# S905D_MIC_V1_1.net
KiCad netlist of a schematic drawn in Altium Designer
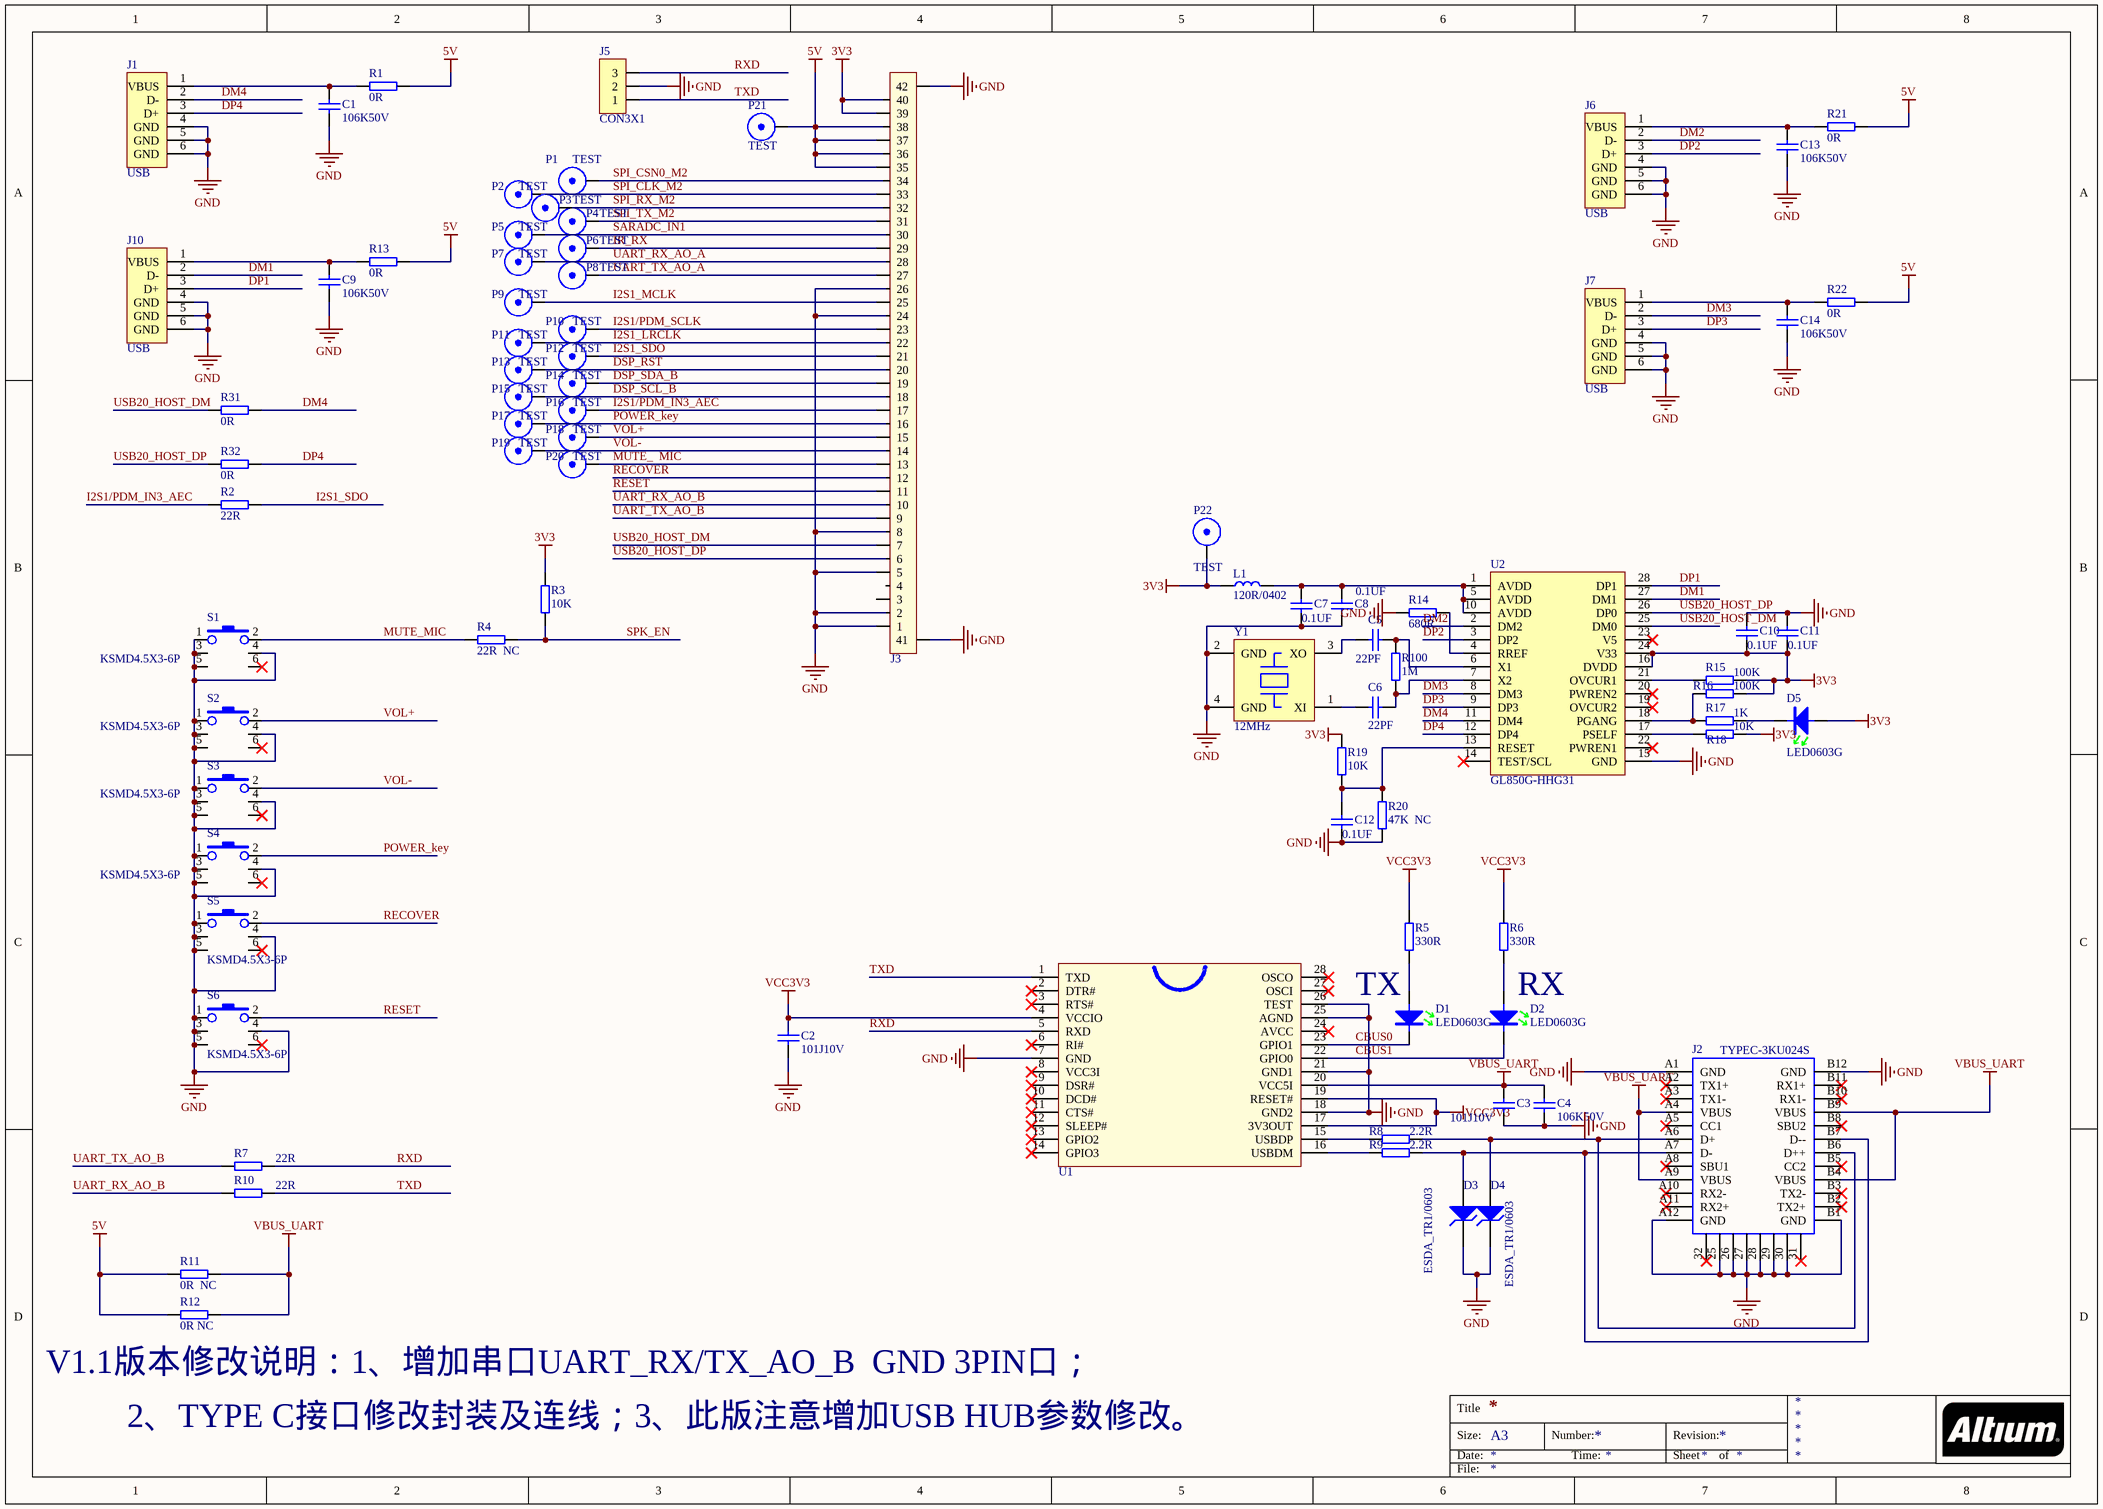
[diagram p0: S905D_MIC_V1.1.SchDoc]

(export (version "E")
  (design (tool "Eeschema 10.0.6"))
  (components
    (comp (ref "C1")
      (value "106K50V")
      (footprint "C0603")
      (description "贴片电容-陶瓷")
      (libsource (lib "AIWAC-bolsterV01") (part "C0603X7R-106K50V"))
    )
    (comp (ref "C2")
      (value "101J10V")
      (footprint "C0402")
      (description "贴片电容-陶瓷")
      (libsource (lib "AIWAC-bolsterV01") (part "C0402X7R-101J10V"))
    )
    (comp (ref "C3")
      (value "101J10V")
      (footprint "C0402")
      (description "贴片电容-陶瓷")
      (libsource (lib "AIWAC-bolsterV01") (part "C0402X7R-101J10V"))
    )
    (comp (ref "C4")
      (value "106K50V")
      (footprint "C0603")
      (description "贴片电容-陶瓷")
      (libsource (lib "AIWAC-bolsterV01") (part "C0603X7R-106K50V"))
    )
    (comp (ref "C5")
      (value "22PF")
      (footprint "C0402")
      (description "贴片电容-陶瓷")
      (libsource (lib "AIWAC-bolsterV01") (part "C0402X7R-101J10V"))
    )
    (comp (ref "C6")
      (value "22PF")
      (footprint "C0402")
      (description "贴片电容-陶瓷")
      (libsource (lib "AIWAC-bolsterV01") (part "C0402X7R-101J10V"))
    )
    (comp (ref "C7")
      (value "0.1UF")
      (footprint "C0402")
      (description "贴片电容-陶瓷")
      (libsource (lib "AIWAC-bolsterV01") (part "C0402X7R-101J10V"))
    )
    (comp (ref "C8")
      (value "0.1UF")
      (footprint "C0402")
      (description "贴片电容-陶瓷")
      (libsource (lib "AIWAC-bolsterV01") (part "C0402X7R-101J10V"))
    )
    (comp (ref "C9")
      (value "106K50V")
      (footprint "C0603")
      (description "贴片电容-陶瓷")
      (libsource (lib "AIWAC-bolsterV01") (part "C0603X7R-106K50V"))
    )
    (comp (ref "C10")
      (value "0.1UF")
      (footprint "C0402")
      (description "贴片电容-陶瓷")
      (libsource (lib "AIWAC-bolsterV01") (part "C0402X7R-101J10V"))
    )
    (comp (ref "C11")
      (value "0.1UF")
      (footprint "C0402")
      (description "贴片电容-陶瓷")
      (libsource (lib "AIWAC-bolsterV01") (part "C0402X7R-101J10V"))
    )
    (comp (ref "C12")
      (value "0.1UF")
      (footprint "C0402")
      (description "贴片电容-陶瓷")
      (libsource (lib "AIWAC-bolsterV01") (part "C0402X7R-101J10V"))
    )
    (comp (ref "C13")
      (value "106K50V")
      (footprint "C0603")
      (description "贴片电容-陶瓷")
      (libsource (lib "AIWAC-bolsterV01") (part "C0603X7R-106K50V"))
    )
    (comp (ref "C14")
      (value "106K50V")
      (footprint "C0603")
      (description "贴片电容-陶瓷")
      (libsource (lib "AIWAC-bolsterV01") (part "C0603X7R-106K50V"))
    )
    (comp (ref "D1")
      (value "LED0603G")
      (footprint "D-LED0603G")
      (description "贴片二极管-LED")
      (libsource (lib "AIWAC-bolsterV01") (part "DLED-0603-G"))
    )
    (comp (ref "D2")
      (value "LED0603G")
      (footprint "D-LED0603G")
      (description "贴片二极管-LED")
      (libsource (lib "AIWAC-bolsterV01") (part "DLED-0603-G"))
    )
    (comp (ref "D3")
      (value "ESDA_TR1/0603")
      (footprint "HS_0603D")
      (description "Zener Diode")
      (fields (field (name "PUBLISHER") "*"))
      (libsource (lib "1_1") (part "D Zener"))
    )
    (comp (ref "D4")
      (value "ESDA_TR1/0603")
      (footprint "HS_0603D")
      (description "Zener Diode")
      (fields (field (name "PUBLISHER") "*"))
      (libsource (lib "1_1") (part "D Zener"))
    )
    (comp (ref "D5")
      (value "LED0603G")
      (footprint "D-LED0603G")
      (description "贴片二极管-LED")
      (libsource (lib "AIWAC-bolsterV01") (part "DLED-0603-G"))
    )
    (comp (ref "J1") (value "USB") (footprint "USB-AD") (libsource (lib "AIWAC-bolsterV01") (part "USB")))
    (comp (ref "J2")
      (value "TYPEC-3KU024S")
      (footprint "MICRO -TYPE C")
      (description "DIP Switch")
      (fields (field (name "PUBLISHER") "Altium Limited"))
      (libsource (lib "AIWAC-bolsterV01") (part "TYPEC-3KU024S"))
    )
    (comp (ref "J3")
      (value "FH34SRJ-40S")
      (footprint "AIWAC-bolsterV01:FH34SRJ-40S")
      (description "贴片FPC40PIN插座")
      (libsource (lib "AIWAC-bolsterV01") (part "SFH34SRJ-40S"))
    )
    (comp (ref "J5")
      (value "CON3X1")
      (footprint "XH2.54-3P - 弯插")
      (libsource (lib "HW335-Multimedia") (part "CON3X1"))
    )
    (comp (ref "J6") (value "USB") (footprint "USB-AD") (libsource (lib "AIWAC-bolsterV01") (part "USB")))
    (comp (ref "J7") (value "USB") (footprint "USB-AD") (libsource (lib "AIWAC-bolsterV01") (part "USB")))
    (comp (ref "J10") (value "USB") (footprint "USB-AD") (libsource (lib "AIWAC-bolsterV01") (part "USB")))
    (comp (ref "L1")
      (value "120R/0402")
      (footprint "C0402")
      (description "贴片电感-屏蔽")
      (libsource (lib "AIWAC-bolsterV01") (part "3.3uH"))
    )
    (comp (ref "P1")
      (value "TEST")
      (footprint "TP")
      (description "BNC Elbow Connector")
      (fields (field (name "PUBLISHER") "Altium Limited"))
      (libsource (lib "XU-GENARAL SCH") (part "TEST"))
    )
    (comp (ref "P2")
      (value "TEST")
      (footprint "TP")
      (description "BNC Elbow Connector")
      (fields (field (name "PUBLISHER") "Altium Limited"))
      (libsource (lib "XU-GENARAL SCH") (part "TEST"))
    )
    (comp (ref "P3")
      (value "TEST")
      (footprint "TP")
      (description "BNC Elbow Connector")
      (fields (field (name "PUBLISHER") "Altium Limited"))
      (libsource (lib "XU-GENARAL SCH") (part "TEST"))
    )
    (comp (ref "P4")
      (value "TEST")
      (footprint "TP")
      (description "BNC Elbow Connector")
      (fields (field (name "PUBLISHER") "Altium Limited"))
      (libsource (lib "XU-GENARAL SCH") (part "TEST"))
    )
    (comp (ref "P5")
      (value "TEST")
      (footprint "TP")
      (description "BNC Elbow Connector")
      (fields (field (name "PUBLISHER") "Altium Limited"))
      (libsource (lib "XU-GENARAL SCH") (part "TEST"))
    )
    (comp (ref "P6")
      (value "TEST")
      (footprint "TP")
      (description "BNC Elbow Connector")
      (fields (field (name "PUBLISHER") "Altium Limited"))
      (libsource (lib "XU-GENARAL SCH") (part "TEST"))
    )
    (comp (ref "P7")
      (value "TEST")
      (footprint "TP")
      (description "BNC Elbow Connector")
      (fields (field (name "PUBLISHER") "Altium Limited"))
      (libsource (lib "XU-GENARAL SCH") (part "TEST"))
    )
    (comp (ref "P8")
      (value "TEST")
      (footprint "TP")
      (description "BNC Elbow Connector")
      (fields (field (name "PUBLISHER") "Altium Limited"))
      (libsource (lib "XU-GENARAL SCH") (part "TEST"))
    )
    (comp (ref "P9")
      (value "TEST")
      (footprint "TP")
      (description "BNC Elbow Connector")
      (fields (field (name "PUBLISHER") "Altium Limited"))
      (libsource (lib "XU-GENARAL SCH") (part "TEST"))
    )
    (comp (ref "P10")
      (value "TEST")
      (footprint "TP")
      (description "BNC Elbow Connector")
      (fields (field (name "PUBLISHER") "Altium Limited"))
      (libsource (lib "XU-GENARAL SCH") (part "TEST"))
    )
    (comp (ref "P11")
      (value "TEST")
      (footprint "TP")
      (description "BNC Elbow Connector")
      (fields (field (name "PUBLISHER") "Altium Limited"))
      (libsource (lib "XU-GENARAL SCH") (part "TEST"))
    )
    (comp (ref "P12")
      (value "TEST")
      (footprint "TP")
      (description "BNC Elbow Connector")
      (fields (field (name "PUBLISHER") "Altium Limited"))
      (libsource (lib "XU-GENARAL SCH") (part "TEST"))
    )
    (comp (ref "P13")
      (value "TEST")
      (footprint "TP")
      (description "BNC Elbow Connector")
      (fields (field (name "PUBLISHER") "Altium Limited"))
      (libsource (lib "XU-GENARAL SCH") (part "TEST"))
    )
    (comp (ref "P14")
      (value "TEST")
      (footprint "TP")
      (description "BNC Elbow Connector")
      (fields (field (name "PUBLISHER") "Altium Limited"))
      (libsource (lib "XU-GENARAL SCH") (part "TEST"))
    )
    (comp (ref "P15")
      (value "TEST")
      (footprint "TP")
      (description "BNC Elbow Connector")
      (fields (field (name "PUBLISHER") "Altium Limited"))
      (libsource (lib "XU-GENARAL SCH") (part "TEST"))
    )
    (comp (ref "P16")
      (value "TEST")
      (footprint "TP")
      (description "BNC Elbow Connector")
      (fields (field (name "PUBLISHER") "Altium Limited"))
      (libsource (lib "XU-GENARAL SCH") (part "TEST"))
    )
    (comp (ref "P17")
      (value "TEST")
      (footprint "TP")
      (description "BNC Elbow Connector")
      (fields (field (name "PUBLISHER") "Altium Limited"))
      (libsource (lib "XU-GENARAL SCH") (part "TEST"))
    )
    (comp (ref "P18")
      (value "TEST")
      (footprint "TP")
      (description "BNC Elbow Connector")
      (fields (field (name "PUBLISHER") "Altium Limited"))
      (libsource (lib "XU-GENARAL SCH") (part "TEST"))
    )
    (comp (ref "P19")
      (value "TEST")
      (footprint "TP")
      (description "BNC Elbow Connector")
      (fields (field (name "PUBLISHER") "Altium Limited"))
      (libsource (lib "XU-GENARAL SCH") (part "TEST"))
    )
    (comp (ref "P20")
      (value "TEST")
      (footprint "TP")
      (description "BNC Elbow Connector")
      (fields (field (name "PUBLISHER") "Altium Limited"))
      (libsource (lib "XU-GENARAL SCH") (part "TEST"))
    )
    (comp (ref "P21")
      (value "TEST")
      (footprint "TP")
      (description "BNC Elbow Connector")
      (fields (field (name "PUBLISHER") "Altium Limited"))
      (libsource (lib "XU-GENARAL SCH") (part "TEST"))
    )
    (comp (ref "P22")
      (value "TEST")
      (footprint "TP")
      (description "BNC Elbow Connector")
      (fields (field (name "PUBLISHER") "Altium Limited"))
      (libsource (lib "XU-GENARAL SCH") (part "TEST"))
    )
    (comp (ref "R1")
      (value "0R")
      (footprint "R0603")
      (description "贴片电阻-通用")
      (libsource (lib "AIWAC-bolsterV01") (part "R0603-0R"))
    )
    (comp (ref "R2")
      (value "22R")
      (footprint "R0402")
      (description "贴片电阻-通用")
      (libsource (lib "AIWAC-bolsterV01") (part "R0402-1KF"))
    )
    (comp (ref "R3")
      (value "10K")
      (footprint "R0402")
      (description "贴片电阻-通用")
      (libsource (lib "AIWAC-bolsterV01") (part "R0402-1KF"))
    )
    (comp (ref "R4")
      (value "22R  NC")
      (footprint "R0402")
      (description "贴片电阻-通用")
      (libsource (lib "AIWAC-bolsterV01") (part "R0402-1KF"))
    )
    (comp (ref "R5")
      (value "330R")
      (footprint "R0402")
      (description "贴片电阻-通用")
      (libsource (lib "AIWAC-bolsterV01") (part "R0402-1KF"))
    )
    (comp (ref "R6")
      (value "330R")
      (footprint "R0402")
      (description "贴片电阻-通用")
      (libsource (lib "AIWAC-bolsterV01") (part "R0402-1KF"))
    )
    (comp (ref "R7")
      (value "22R")
      (footprint "R0402")
      (description "贴片电阻-通用")
      (libsource (lib "AIWAC-bolsterV01") (part "R0402-1KF"))
    )
    (comp (ref "R8")
      (value "2.2R")
      (footprint "R0402")
      (description "贴片电阻-通用")
      (libsource (lib "AIWAC-bolsterV01") (part "R0402-1KF"))
    )
    (comp (ref "R9")
      (value "2.2R")
      (footprint "R0402")
      (description "贴片电阻-通用")
      (libsource (lib "AIWAC-bolsterV01") (part "R0402-1KF"))
    )
    (comp (ref "R10")
      (value "22R")
      (footprint "R0402")
      (description "贴片电阻-通用")
      (libsource (lib "AIWAC-bolsterV01") (part "R0402-1KF"))
    )
    (comp (ref "R11")
      (value "0R  NC")
      (footprint "R0603")
      (description "贴片电阻-通用")
      (libsource (lib "AIWAC-bolsterV01") (part "R0603-0R"))
    )
    (comp (ref "R12")
      (value "0R NC")
      (footprint "R0603")
      (description "贴片电阻-通用")
      (libsource (lib "AIWAC-bolsterV01") (part "R0603-0R"))
    )
    (comp (ref "R13")
      (value "0R")
      (footprint "R0603")
      (description "贴片电阻-通用")
      (libsource (lib "AIWAC-bolsterV01") (part "R0603-0R"))
    )
    (comp (ref "R14")
      (value "680R")
      (footprint "R0402")
      (description "贴片电阻-通用")
      (libsource (lib "AIWAC-bolsterV01") (part "R0402-1KF"))
    )
    (comp (ref "R15")
      (value "100K")
      (footprint "R0402")
      (description "贴片电阻-通用")
      (libsource (lib "AIWAC-bolsterV01") (part "R0402-1KF"))
    )
    (comp (ref "R16")
      (value "100K")
      (footprint "R0402")
      (description "贴片电阻-通用")
      (libsource (lib "AIWAC-bolsterV01") (part "R0402-1KF"))
    )
    (comp (ref "R17")
      (value "1K")
      (footprint "R0402")
      (description "贴片电阻-通用")
      (libsource (lib "AIWAC-bolsterV01") (part "R0402-1KF"))
    )
    (comp (ref "R18")
      (value "10K")
      (footprint "R0402")
      (description "贴片电阻-通用")
      (libsource (lib "AIWAC-bolsterV01") (part "R0402-1KF"))
    )
    (comp (ref "R19")
      (value "10K")
      (footprint "R0402")
      (description "贴片电阻-通用")
      (libsource (lib "AIWAC-bolsterV01") (part "R0402-1KF"))
    )
    (comp (ref "R20")
      (value "47K  NC")
      (footprint "R0402")
      (description "贴片电阻-通用")
      (libsource (lib "AIWAC-bolsterV01") (part "R0402-1KF"))
    )
    (comp (ref "R21")
      (value "0R")
      (footprint "R0603")
      (description "贴片电阻-通用")
      (libsource (lib "AIWAC-bolsterV01") (part "R0603-0R"))
    )
    (comp (ref "R22")
      (value "0R")
      (footprint "R0603")
      (description "贴片电阻-通用")
      (libsource (lib "AIWAC-bolsterV01") (part "R0603-0R"))
    )
    (comp (ref "R31")
      (value "0R")
      (footprint "R0402")
      (description "贴片电阻-通用")
      (libsource (lib "AIWAC-bolsterV01") (part "R0402-1KF"))
    )
    (comp (ref "R32")
      (value "0R")
      (footprint "R0402")
      (description "贴片电阻-通用")
      (libsource (lib "AIWAC-bolsterV01") (part "R0402-1KF"))
    )
    (comp (ref "R100")
      (value "1M")
      (footprint "R0402")
      (description "贴片电阻-通用")
      (libsource (lib "AIWAC-bolsterV01") (part "R0402-1KF"))
    )
    (comp (ref "S1")
      (value "KSMD4.5X3-6P")
      (footprint "SKRTLAE010")
      (description "贴片侧按键")
      (libsource (lib "AIWAC-bolsterV01") (part "KSMD4.5X3-6P"))
    )
    (comp (ref "S2")
      (value "KSMD4.5X3-6P")
      (footprint "SKRTLAE010")
      (description "贴片侧按键")
      (libsource (lib "AIWAC-bolsterV01") (part "KSMD4.5X3-6P"))
    )
    (comp (ref "S3")
      (value "KSMD4.5X3-6P")
      (footprint "AIWAC-bolsterV01:SKRTLAE010")
      (description "贴片侧按键")
      (libsource (lib "AIWAC-bolsterV01") (part "KSMD4.5X3-6P"))
    )
    (comp (ref "S4")
      (value "KSMD4.5X3-6P")
      (footprint "AIWAC-bolsterV01:SKRTLAE010")
      (description "贴片侧按键")
      (libsource (lib "AIWAC-bolsterV01") (part "KSMD4.5X3-6P"))
    )
    (comp (ref "S5")
      (value "KSMD4.5X3-6P")
      (footprint "SKRTLAE010")
      (description "贴片侧按键")
      (libsource (lib "AIWAC-bolsterV01") (part "KSMD4.5X3-6P"))
    )
    (comp (ref "S6")
      (value "KSMD4.5X3-6P")
      (footprint "SKRTLAE010")
      (description "贴片侧按键")
      (libsource (lib "AIWAC-bolsterV01") (part "KSMD4.5X3-6P"))
    )
    (comp (ref "U1")
      (value "FT232R_SOP28")
      (footprint "AIWAC-bolsterV01:SSOP28")
      (description "USB 转串口芯片")
      (libsource (lib "AIWAC-bolsterV01") (part "FT232R_SOP28"))
    )
    (comp (ref "U2")
      (value "GL850G-HHG31")
      (footprint "SSOP28")
      (libsource (lib "AIWAC-bolsterV01") (part "GL850G-HHG31"))
    )
    (comp (ref "Y1")
      (value "12MHz")
      (footprint "AIWAC-bolsterV01:Y-CPX-32GA-4P")
      (description "晶振-贴片无源")
      (libsource (lib "AIWAC-bolsterV01") (part "YC-26MHz"))
    )
  )
  (nets
    (net (code "1") (name "/CBUS0") (class "Default")
      (node (ref "D1") (pin "2") (pinfunction "2_2") (pintype "passive"))
      (node (ref "U1") (pin "23") (pinfunction "GPIO1_23") (pintype "passive"))
    )
    (net (code "2") (name "/CBUS1") (class "Default")
      (node (ref "D2") (pin "2") (pinfunction "2_2") (pintype "passive"))
      (node (ref "U1") (pin "22") (pinfunction "GPIO0_22") (pintype "passive"))
    )
    (net (code "3") (name "/DM1") (class "Default")
      (node (ref "J10") (pin "2") (pinfunction "D-_2") (pintype "passive"))
      (node (ref "U2") (pin "27") (pinfunction "DM1_27") (pintype "passive"))
    )
    (net (code "4") (name "/DM2") (class "Default")
      (node (ref "J6") (pin "2") (pinfunction "D-_2") (pintype "passive"))
      (node (ref "U2") (pin "2") (pinfunction "DM2_2") (pintype "passive"))
    )
    (net (code "5") (name "/DM3") (class "Default")
      (node (ref "J7") (pin "2") (pinfunction "D-_2") (pintype "passive"))
      (node (ref "U2") (pin "8") (pinfunction "DM3_8") (pintype "passive"))
    )
    (net (code "6") (name "/DM4") (class "Default")
      (node (ref "J1") (pin "2") (pinfunction "D-_2") (pintype "passive"))
      (node (ref "R31") (pin "2") (pinfunction "2_2") (pintype "passive"))
      (node (ref "U2") (pin "11") (pinfunction "DM4_11") (pintype "passive"))
    )
    (net (code "7") (name "/DP1") (class "Default")
      (node (ref "J10") (pin "3") (pinfunction "D+_3") (pintype "passive"))
      (node (ref "U2") (pin "28") (pinfunction "DP1_28") (pintype "passive"))
    )
    (net (code "8") (name "/DP2") (class "Default")
      (node (ref "J6") (pin "3") (pinfunction "D+_3") (pintype "passive"))
      (node (ref "U2") (pin "3") (pinfunction "DP2_3") (pintype "passive"))
    )
    (net (code "9") (name "/DP3") (class "Default")
      (node (ref "J7") (pin "3") (pinfunction "D+_3") (pintype "passive"))
      (node (ref "U2") (pin "9") (pinfunction "DP3_9") (pintype "passive"))
    )
    (net (code "10") (name "/DP4") (class "Default")
      (node (ref "J1") (pin "3") (pinfunction "D+_3") (pintype "passive"))
      (node (ref "R32") (pin "2") (pinfunction "2_2") (pintype "passive"))
      (node (ref "U2") (pin "12") (pinfunction "DP4_12") (pintype "passive"))
    )
    (net (code "11") (name "/DSP_RST") (class "Default")
      (node (ref "J3") (pin "20") (pinfunction "20_20") (pintype "passive"))
      (node (ref "P13") (pin "1") (pinfunction "Y1_1") (pintype "passive"))
    )
    (net (code "12") (name "/DSP_SCL_B") (class "Default")
      (node (ref "J3") (pin "18") (pinfunction "18_18") (pintype "passive"))
      (node (ref "P15") (pin "1") (pinfunction "Y1_1") (pintype "passive"))
    )
    (net (code "13") (name "/DSP_SDA_B") (class "Default")
      (node (ref "J3") (pin "19") (pinfunction "19_19") (pintype "passive"))
      (node (ref "P14") (pin "1") (pinfunction "Y1_1") (pintype "passive"))
    )
    (net (code "14") (name "/I2S1_LRCLK") (class "Default")
      (node (ref "J3") (pin "22") (pinfunction "22_22") (pintype "passive"))
      (node (ref "P11") (pin "1") (pinfunction "Y1_1") (pintype "passive"))
    )
    (net (code "15") (name "/I2S1_MCLK") (class "Default")
      (node (ref "J3") (pin "25") (pinfunction "25_25") (pintype "passive"))
      (node (ref "P9") (pin "1") (pinfunction "Y1_1") (pintype "passive"))
    )
    (net (code "16") (name "/I2S1_SDO") (class "Default")
      (node (ref "J3") (pin "21") (pinfunction "21_21") (pintype "passive"))
      (node (ref "P12") (pin "1") (pinfunction "Y1_1") (pintype "passive"))
      (node (ref "R2") (pin "2") (pinfunction "2_2") (pintype "passive"))
    )
    (net (code "17") (name "/I2S1{slash}PDM_IN3_AEC") (class "Default")
      (node (ref "J3") (pin "17") (pinfunction "17_17") (pintype "passive"))
      (node (ref "P16") (pin "1") (pinfunction "Y1_1") (pintype "passive"))
      (node (ref "R2") (pin "1") (pinfunction "1_1") (pintype "passive"))
    )
    (net (code "18") (name "/I2S1{slash}PDM_SCLK") (class "Default")
      (node (ref "J3") (pin "23") (pinfunction "23_23") (pintype "passive"))
      (node (ref "P10") (pin "1") (pinfunction "Y1_1") (pintype "passive"))
    )
    (net (code "19") (name "/IR_RX") (class "Default")
      (node (ref "J3") (pin "29") (pinfunction "29_29") (pintype "passive"))
      (node (ref "P6") (pin "1") (pinfunction "Y1_1") (pintype "passive"))
    )
    (net (code "20") (name "/MUTE_  MIC") (class "Default")
      (node (ref "J3") (pin "13") (pinfunction "13_13") (pintype "passive"))
      (node (ref "P20") (pin "1") (pinfunction "Y1_1") (pintype "passive"))
    )
    (net (code "21") (name "/MUTE_MIC") (class "Default")
      (node (ref "R4") (pin "1") (pinfunction "1_1") (pintype "passive"))
      (node (ref "S1") (pin "2") (pinfunction "2_2") (pintype "passive"))
    )
    (net (code "22") (name "/POWER_key") (class "Default")
      (node (ref "J3") (pin "16") (pinfunction "16_16") (pintype "passive"))
      (node (ref "P17") (pin "1") (pinfunction "Y1_1") (pintype "passive"))
      (node (ref "S4") (pin "2") (pinfunction "2_2") (pintype "passive"))
    )
    (net (code "23") (name "/RECOVER") (class "Default")
      (node (ref "J3") (pin "12") (pinfunction "12_12") (pintype "passive"))
      (node (ref "S5") (pin "2") (pinfunction "2_2") (pintype "passive"))
    )
    (net (code "24") (name "/RESET") (class "Default")
      (node (ref "J3") (pin "11") (pinfunction "11_11") (pintype "passive"))
      (node (ref "S6") (pin "2") (pinfunction "2_2") (pintype "passive"))
    )
    (net (code "25") (name "/RXD") (class "Default")
      (node (ref "J5") (pin "3") (pinfunction "3_3") (pintype "passive"))
      (node (ref "R7") (pin "2") (pinfunction "2_2") (pintype "passive"))
      (node (ref "U1") (pin "5") (pinfunction "RXD_5") (pintype "passive"))
    )
    (net (code "26") (name "/SARADC_IN1") (class "Default")
      (node (ref "J3") (pin "30") (pinfunction "30_30") (pintype "passive"))
      (node (ref "P5") (pin "1") (pinfunction "Y1_1") (pintype "passive"))
    )
    (net (code "27") (name "/SPI_CLK_M2") (class "Default")
      (node (ref "J3") (pin "33") (pinfunction "33_33") (pintype "passive"))
      (node (ref "P2") (pin "1") (pinfunction "Y1_1") (pintype "passive"))
    )
    (net (code "28") (name "/SPI_CSN0_M2") (class "Default")
      (node (ref "J3") (pin "34") (pinfunction "34_34") (pintype "passive"))
      (node (ref "P1") (pin "1") (pinfunction "Y1_1") (pintype "passive"))
    )
    (net (code "29") (name "/SPI_RX_M2") (class "Default")
      (node (ref "J3") (pin "32") (pinfunction "32_32") (pintype "passive"))
      (node (ref "P3") (pin "1") (pinfunction "Y1_1") (pintype "passive"))
    )
    (net (code "30") (name "/SPI_TX_M2") (class "Default")
      (node (ref "J3") (pin "31") (pinfunction "31_31") (pintype "passive"))
      (node (ref "P4") (pin "1") (pinfunction "Y1_1") (pintype "passive"))
    )
    (net (code "31") (name "/SPK_EN") (class "Default")
      (node (ref "R3") (pin "1") (pinfunction "1_1") (pintype "passive"))
      (node (ref "R4") (pin "2") (pinfunction "2_2") (pintype "passive"))
    )
    (net (code "32") (name "/TXD") (class "Default")
      (node (ref "J5") (pin "1") (pinfunction "1_1") (pintype "passive"))
      (node (ref "R10") (pin "2") (pinfunction "2_2") (pintype "passive"))
      (node (ref "U1") (pin "1") (pinfunction "TXD_1") (pintype "passive"))
    )
    (net (code "33") (name "/UART_RX_AO_A") (class "Default")
      (node (ref "J3") (pin "28") (pinfunction "28_28") (pintype "passive"))
      (node (ref "P7") (pin "1") (pinfunction "Y1_1") (pintype "passive"))
    )
    (net (code "34") (name "/UART_RX_AO_B") (class "Default")
      (node (ref "J3") (pin "10") (pinfunction "10_10") (pintype "passive"))
      (node (ref "R10") (pin "1") (pinfunction "1_1") (pintype "passive"))
    )
    (net (code "35") (name "/UART_TX_AO_A") (class "Default")
      (node (ref "J3") (pin "27") (pinfunction "27_27") (pintype "passive"))
      (node (ref "P8") (pin "1") (pinfunction "Y1_1") (pintype "passive"))
    )
    (net (code "36") (name "/UART_TX_AO_B") (class "Default")
      (node (ref "J3") (pin "9") (pinfunction "9_9") (pintype "passive"))
      (node (ref "R7") (pin "1") (pinfunction "1_1") (pintype "passive"))
    )
    (net (code "37") (name "/USB20_HOST_DM") (class "Default")
      (node (ref "J3") (pin "7") (pinfunction "7_7") (pintype "passive"))
      (node (ref "R31") (pin "1") (pinfunction "1_1") (pintype "passive"))
      (node (ref "U2") (pin "25") (pinfunction "DM0_25") (pintype "passive"))
    )
    (net (code "38") (name "/USB20_HOST_DP") (class "Default")
      (node (ref "J3") (pin "6") (pinfunction "6_6") (pintype "passive"))
      (node (ref "R32") (pin "1") (pinfunction "1_1") (pintype "passive"))
      (node (ref "U2") (pin "26") (pinfunction "DP0_26") (pintype "passive"))
    )
    (net (code "39") (name "/VOL+") (class "Default")
      (node (ref "J3") (pin "15") (pinfunction "15_15") (pintype "passive"))
      (node (ref "P18") (pin "1") (pinfunction "Y1_1") (pintype "passive"))
      (node (ref "S2") (pin "2") (pinfunction "2_2") (pintype "passive"))
    )
    (net (code "40") (name "/VOL-") (class "Default")
      (node (ref "J3") (pin "14") (pinfunction "14_14") (pintype "passive"))
      (node (ref "P19") (pin "1") (pinfunction "Y1_1") (pintype "passive"))
      (node (ref "S3") (pin "2") (pinfunction "2_2") (pintype "passive"))
    )
    (net (code "41") (name "3V3") (class "Default")
      (node (ref "C10") (pin "2") (pinfunction "2_2") (pintype "passive"))
      (node (ref "C11") (pin "2") (pinfunction "2_2") (pintype "passive"))
      (node (ref "D5") (pin "1") (pinfunction "1_1") (pintype "passive"))
      (node (ref "J3") (pin "39") (pinfunction "39_39") (pintype "passive"))
      (node (ref "J3") (pin "40") (pinfunction "40_40") (pintype "passive"))
      (node (ref "L1") (pin "1") (pinfunction "1_1") (pintype "passive"))
      (node (ref "P22") (pin "1") (pinfunction "Y1_1") (pintype "passive"))
      (node (ref "R15") (pin "1") (pinfunction "1_1") (pintype "passive"))
      (node (ref "R16") (pin "1") (pinfunction "1_1") (pintype "passive"))
      (node (ref "R18") (pin "1") (pinfunction "1_1") (pintype "passive"))
      (node (ref "R19") (pin "2") (pinfunction "2_2") (pintype "passive"))
      (node (ref "R3") (pin "2") (pinfunction "2_2") (pintype "passive"))
      (node (ref "U2") (pin "16") (pinfunction "DVDD_16") (pintype "passive"))
      (node (ref "U2") (pin "24") (pinfunction "V33_24") (pintype "passive"))
    )
    (net (code "42") (name "5V") (class "Default")
      (node (ref "J3") (pin "35") (pinfunction "35_35") (pintype "passive"))
      (node (ref "J3") (pin "36") (pinfunction "36_36") (pintype "passive"))
      (node (ref "J3") (pin "37") (pinfunction "37_37") (pintype "passive"))
      (node (ref "J3") (pin "38") (pinfunction "38_38") (pintype "passive"))
      (node (ref "P21") (pin "1") (pinfunction "Y1_1") (pintype "passive"))
      (node (ref "R1") (pin "2") (pinfunction "2_2") (pintype "passive"))
      (node (ref "R11") (pin "2") (pinfunction "2_2") (pintype "passive"))
      (node (ref "R12") (pin "1") (pinfunction "1_1") (pintype "passive"))
      (node (ref "R13") (pin "2") (pinfunction "2_2") (pintype "passive"))
      (node (ref "R21") (pin "2") (pinfunction "2_2") (pintype "passive"))
      (node (ref "R22") (pin "2") (pinfunction "2_2") (pintype "passive"))
    )
    (net (code "43") (name "GND") (class "Default")
      (node (ref "C1") (pin "2") (pinfunction "2_2") (pintype "passive"))
      (node (ref "C10") (pin "1") (pinfunction "1_1") (pintype "passive"))
      (node (ref "C11") (pin "1") (pinfunction "1_1") (pintype "passive"))
      (node (ref "C12") (pin "2") (pinfunction "2_2") (pintype "passive"))
      (node (ref "C13") (pin "2") (pinfunction "2_2") (pintype "passive"))
      (node (ref "C14") (pin "2") (pinfunction "2_2") (pintype "passive"))
      (node (ref "C2") (pin "2") (pinfunction "2_2") (pintype "passive"))
      (node (ref "C3") (pin "2") (pinfunction "2_2") (pintype "passive"))
      (node (ref "C4") (pin "2") (pinfunction "2_2") (pintype "passive"))
      (node (ref "C7") (pin "2") (pinfunction "2_2") (pintype "passive"))
      (node (ref "C8") (pin "2") (pinfunction "2_2") (pintype "passive"))
      (node (ref "C9") (pin "2") (pinfunction "2_2") (pintype "passive"))
      (node (ref "D3") (pin "2") (pinfunction "K_2") (pintype "passive"))
      (node (ref "D4") (pin "2") (pinfunction "K_2") (pintype "passive"))
      (node (ref "J1") (pin "4") (pinfunction "GND_4") (pintype "passive"))
      (node (ref "J1") (pin "5") (pinfunction "GND_5") (pintype "passive"))
      (node (ref "J1") (pin "6") (pinfunction "GND_6") (pintype "passive"))
      (node (ref "J10") (pin "4") (pinfunction "GND_4") (pintype "passive"))
      (node (ref "J10") (pin "5") (pinfunction "GND_5") (pintype "passive"))
      (node (ref "J10") (pin "6") (pinfunction "GND_6") (pintype "passive"))
      (node (ref "J2") (pin "25") (pinfunction "25_25") (pintype "passive"))
      (node (ref "J2") (pin "26") (pinfunction "B13_26") (pintype "passive"))
      (node (ref "J2") (pin "27") (pinfunction "B14_27") (pintype "passive"))
      (node (ref "J2") (pin "28") (pinfunction "B15_28") (pintype "passive"))
      (node (ref "J2") (pin "29") (pinfunction "B16_29") (pintype "passive"))
      (node (ref "J2") (pin "30") (pinfunction "B17_30") (pintype "passive"))
      (node (ref "J2") (pin "A1") (pinfunction "GND_A1") (pintype "passive"))
      (node (ref "J2") (pin "A12") (pinfunction "GND_A12") (pintype "passive"))
      (node (ref "J2") (pin "B1") (pinfunction "GND_B1") (pintype "passive"))
      (node (ref "J2") (pin "B12") (pinfunction "GND_B12") (pintype "passive"))
      (node (ref "J3") (pin "1") (pinfunction "1_1") (pintype "passive"))
      (node (ref "J3") (pin "2") (pinfunction "2_2") (pintype "passive"))
      (node (ref "J3") (pin "24") (pinfunction "24_24") (pintype "passive"))
      (node (ref "J3") (pin "26") (pinfunction "26_26") (pintype "passive"))
      (node (ref "J3") (pin "41") (pinfunction "41_41") (pintype "passive"))
      (node (ref "J3") (pin "42") (pinfunction "42_42") (pintype "passive"))
      (node (ref "J3") (pin "5") (pinfunction "5_5") (pintype "passive"))
      (node (ref "J3") (pin "8") (pinfunction "8_8") (pintype "passive"))
      (node (ref "J5") (pin "2") (pinfunction "2_2") (pintype "passive"))
      (node (ref "J6") (pin "4") (pinfunction "GND_4") (pintype "passive"))
      (node (ref "J6") (pin "5") (pinfunction "GND_5") (pintype "passive"))
      (node (ref "J6") (pin "6") (pinfunction "GND_6") (pintype "passive"))
      (node (ref "J7") (pin "4") (pinfunction "GND_4") (pintype "passive"))
      (node (ref "J7") (pin "5") (pinfunction "GND_5") (pintype "passive"))
      (node (ref "J7") (pin "6") (pinfunction "GND_6") (pintype "passive"))
      (node (ref "R14") (pin "2") (pinfunction "2_2") (pintype "passive"))
      (node (ref "R20") (pin "1") (pinfunction "1_1") (pintype "passive"))
      (node (ref "S1") (pin "1") (pinfunction "1_1") (pintype "passive"))
      (node (ref "S1") (pin "3") (pinfunction "1_3") (pintype "passive"))
      (node (ref "S1") (pin "4") (pinfunction "2_4") (pintype "passive"))
      (node (ref "S1") (pin "5") (pinfunction "1_5") (pintype "passive"))
      (node (ref "S2") (pin "1") (pinfunction "1_1") (pintype "passive"))
      (node (ref "S2") (pin "3") (pinfunction "1_3") (pintype "passive"))
      (node (ref "S2") (pin "4") (pinfunction "2_4") (pintype "passive"))
      (node (ref "S2") (pin "5") (pinfunction "1_5") (pintype "passive"))
      (node (ref "S3") (pin "1") (pinfunction "1_1") (pintype "passive"))
      (node (ref "S3") (pin "3") (pinfunction "1_3") (pintype "passive"))
      (node (ref "S3") (pin "4") (pinfunction "2_4") (pintype "passive"))
      (node (ref "S3") (pin "5") (pinfunction "1_5") (pintype "passive"))
      (node (ref "S4") (pin "1") (pinfunction "1_1") (pintype "passive"))
      (node (ref "S4") (pin "3") (pinfunction "1_3") (pintype "passive"))
      (node (ref "S4") (pin "4") (pinfunction "2_4") (pintype "passive"))
      (node (ref "S4") (pin "5") (pinfunction "1_5") (pintype "passive"))
      (node (ref "S5") (pin "1") (pinfunction "1_1") (pintype "passive"))
      (node (ref "S5") (pin "3") (pinfunction "1_3") (pintype "passive"))
      (node (ref "S5") (pin "4") (pinfunction "2_4") (pintype "passive"))
      (node (ref "S5") (pin "5") (pinfunction "1_5") (pintype "passive"))
      (node (ref "S6") (pin "1") (pinfunction "1_1") (pintype "passive"))
      (node (ref "S6") (pin "3") (pinfunction "1_3") (pintype "passive"))
      (node (ref "S6") (pin "4") (pinfunction "2_4") (pintype "passive"))
      (node (ref "S6") (pin "5") (pinfunction "1_5") (pintype "passive"))
      (node (ref "U1") (pin "18") (pinfunction "GND2_18") (pintype "passive"))
      (node (ref "U1") (pin "21") (pinfunction "GND1_21") (pintype "passive"))
      (node (ref "U1") (pin "25") (pinfunction "AGND_25") (pintype "passive"))
      (node (ref "U1") (pin "26") (pinfunction "TEST_26") (pintype "passive"))
      (node (ref "U1") (pin "7") (pinfunction "GND_7") (pintype "passive"))
      (node (ref "U2") (pin "15") (pinfunction "GND_15") (pintype "passive"))
      (node (ref "Y1") (pin "2") (pinfunction "GND_2") (pintype "passive"))
      (node (ref "Y1") (pin "4") (pinfunction "GND_4") (pintype "passive"))
    )
    (net (code "44") (name "Net-(C7-Pad1)") (class "Default")
      (node (ref "C7") (pin "1") (pinfunction "1_1") (pintype "passive"))
      (node (ref "C8") (pin "1") (pinfunction "1_1") (pintype "passive"))
      (node (ref "L1") (pin "2") (pinfunction "2_2") (pintype "passive"))
      (node (ref "U2") (pin "1") (pinfunction "AVDD_1") (pintype "passive"))
      (node (ref "U2") (pin "10") (pinfunction "AVDD_10") (pintype "passive"))
      (node (ref "U2") (pin "5") (pinfunction "AVDD_5") (pintype "passive"))
    )
    (net (code "45") (name "Net-(D1-Pad1)") (class "Default")
      (node (ref "D1") (pin "1") (pinfunction "1_1") (pintype "passive"))
      (node (ref "R5") (pin "1") (pinfunction "1_1") (pintype "passive"))
    )
    (net (code "46") (name "Net-(D2-Pad1)") (class "Default")
      (node (ref "D2") (pin "1") (pinfunction "1_1") (pintype "passive"))
      (node (ref "R6") (pin "1") (pinfunction "1_1") (pintype "passive"))
    )
    (net (code "47") (name "Net-(D3-A)") (class "Default")
      (node (ref "D3") (pin "1") (pinfunction "A_1") (pintype "passive"))
      (node (ref "J2") (pin "A7") (pinfunction "D-_A7") (pintype "passive"))
      (node (ref "J2") (pin "B7") (pinfunction "D--_B7") (pintype "passive"))
      (node (ref "R9") (pin "2") (pinfunction "2_2") (pintype "passive"))
    )
    (net (code "48") (name "Net-(D4-A)") (class "Default")
      (node (ref "D4") (pin "1") (pinfunction "A_1") (pintype "passive"))
      (node (ref "J2") (pin "A6") (pinfunction "D+_A6") (pintype "passive"))
      (node (ref "J2") (pin "B6") (pinfunction "D++_B6") (pintype "passive"))
      (node (ref "R8") (pin "2") (pinfunction "2_2") (pintype "passive"))
    )
    (net (code "49") (name "Net-(D5-Pad2)") (class "Default")
      (node (ref "D5") (pin "2") (pinfunction "2_2") (pintype "passive"))
      (node (ref "R17") (pin "1") (pinfunction "1_1") (pintype "passive"))
    )
    (net (code "50") (name "Net-(J1-VBUS)") (class "Default")
      (node (ref "C1") (pin "1") (pinfunction "1_1") (pintype "passive"))
      (node (ref "J1") (pin "1") (pinfunction "VBUS_1") (pintype "passive"))
      (node (ref "R1") (pin "1") (pinfunction "1_1") (pintype "passive"))
    )
    (net (code "51") (name "Net-(J6-VBUS)") (class "Default")
      (node (ref "C13") (pin "1") (pinfunction "1_1") (pintype "passive"))
      (node (ref "J6") (pin "1") (pinfunction "VBUS_1") (pintype "passive"))
      (node (ref "R21") (pin "1") (pinfunction "1_1") (pintype "passive"))
    )
    (net (code "52") (name "Net-(J7-VBUS)") (class "Default")
      (node (ref "C14") (pin "1") (pinfunction "1_1") (pintype "passive"))
      (node (ref "J7") (pin "1") (pinfunction "VBUS_1") (pintype "passive"))
      (node (ref "R22") (pin "1") (pinfunction "1_1") (pintype "passive"))
    )
    (net (code "53") (name "Net-(J10-VBUS)") (class "Default")
      (node (ref "C9") (pin "1") (pinfunction "1_1") (pintype "passive"))
      (node (ref "J10") (pin "1") (pinfunction "VBUS_1") (pintype "passive"))
      (node (ref "R13") (pin "1") (pinfunction "1_1") (pintype "passive"))
    )
    (net (code "54") (name "Net-(U1-USBDM)") (class "Default")
      (node (ref "R9") (pin "1") (pinfunction "1_1") (pintype "passive"))
      (node (ref "U1") (pin "16") (pinfunction "USBDM_16") (pintype "passive"))
    )
    (net (code "55") (name "Net-(U1-USBDP)") (class "Default")
      (node (ref "R8") (pin "1") (pinfunction "1_1") (pintype "passive"))
      (node (ref "U1") (pin "15") (pinfunction "USBDP_15") (pintype "passive"))
    )
    (net (code "56") (name "Net-(U2-OVCUR1)") (class "Default")
      (node (ref "R15") (pin "2") (pinfunction "2_2") (pintype "passive"))
      (node (ref "U2") (pin "21") (pinfunction "OVCUR1_21") (pintype "passive"))
    )
    (net (code "57") (name "Net-(U2-PGANG)") (class "Default")
      (node (ref "R16") (pin "2") (pinfunction "2_2") (pintype "passive"))
      (node (ref "R17") (pin "2") (pinfunction "2_2") (pintype "passive"))
      (node (ref "U2") (pin "18") (pinfunction "PGANG_18") (pintype "passive"))
    )
    (net (code "58") (name "Net-(U2-PSELF)") (class "Default")
      (node (ref "R18") (pin "2") (pinfunction "2_2") (pintype "passive"))
      (node (ref "U2") (pin "17") (pinfunction "PSELF_17") (pintype "passive"))
    )
    (net (code "59") (name "Net-(U2-RESET)") (class "Default")
      (node (ref "C12") (pin "1") (pinfunction "1_1") (pintype "passive"))
      (node (ref "R19") (pin "1") (pinfunction "1_1") (pintype "passive"))
      (node (ref "R20") (pin "2") (pinfunction "2_2") (pintype "passive"))
      (node (ref "U2") (pin "13") (pinfunction "RESET_13") (pintype "passive"))
    )
    (net (code "60") (name "Net-(U2-RREF)") (class "Default")
      (node (ref "R14") (pin "1") (pinfunction "1_1") (pintype "passive"))
      (node (ref "U2") (pin "4") (pinfunction "RREF_4") (pintype "passive"))
    )
    (net (code "61") (name "Net-(U2-X1)") (class "Default")
      (node (ref "C5") (pin "2") (pinfunction "2_2") (pintype "passive"))
      (node (ref "R100") (pin "2") (pinfunction "2_2") (pintype "passive"))
      (node (ref "U2") (pin "6") (pinfunction "X1_6") (pintype "passive"))
    )
    (net (code "62") (name "Net-(U2-X2)") (class "Default")
      (node (ref "C6") (pin "2") (pinfunction "2_2") (pintype "passive"))
      (node (ref "R100") (pin "1") (pinfunction "1_1") (pintype "passive"))
      (node (ref "U2") (pin "7") (pinfunction "X2_7") (pintype "passive"))
    )
    (net (code "63") (name "Net-(Y1-XI)") (class "Default")
      (node (ref "C6") (pin "1") (pinfunction "1_1") (pintype "passive"))
      (node (ref "Y1") (pin "1") (pinfunction "XI_1") (pintype "passive"))
    )
    (net (code "64") (name "Net-(Y1-XO)") (class "Default")
      (node (ref "C5") (pin "1") (pinfunction "1_1") (pintype "passive"))
      (node (ref "Y1") (pin "3") (pinfunction "XO_3") (pintype "passive"))
    )
    (net (code "65") (name "VBUS_UART") (class "Default")
      (node (ref "C3") (pin "1") (pinfunction "1_1") (pintype "passive"))
      (node (ref "C4") (pin "1") (pinfunction "1_1") (pintype "passive"))
      (node (ref "J2") (pin "A4") (pinfunction "VBUS_A4") (pintype "passive"))
      (node (ref "J2") (pin "A9") (pinfunction "VBUS_A9") (pintype "passive"))
      (node (ref "J2") (pin "B4") (pinfunction "VBUS_B4") (pintype "passive"))
      (node (ref "J2") (pin "B9") (pinfunction "VBUS_B9") (pintype "passive"))
      (node (ref "R11") (pin "1") (pinfunction "1_1") (pintype "passive"))
      (node (ref "R12") (pin "2") (pinfunction "2_2") (pintype "passive"))
      (node (ref "U1") (pin "20") (pinfunction "VCC5I_20") (pintype "passive"))
    )
    (net (code "66") (name "VCC3V3") (class "Default")
      (node (ref "C2") (pin "1") (pinfunction "1_1") (pintype "passive"))
      (node (ref "R5") (pin "2") (pinfunction "2_2") (pintype "passive"))
      (node (ref "R6") (pin "2") (pinfunction "2_2") (pintype "passive"))
      (node (ref "U1") (pin "17") (pinfunction "3V3OUT_17") (pintype "passive"))
      (node (ref "U1") (pin "19") (pinfunction "RESET#_19") (pintype "passive"))
      (node (ref "U1") (pin "4") (pinfunction "VCCIO_4") (pintype "passive"))
    )
    (net (code "67") (name "unconnected-(J2-B13-Pad32)") (class "Default")
      (node (ref "J2") (pin "32") (pinfunction "B13_32") (pintype "passive+no_connect"))
    )
    (net (code "68") (name "unconnected-(J2-B18-Pad31)") (class "Default")
      (node (ref "J2") (pin "31") (pinfunction "B18_31") (pintype "passive+no_connect"))
    )
    (net (code "69") (name "unconnected-(J2-CC1-PadA5)") (class "Default")
      (node (ref "J2") (pin "A5") (pinfunction "CC1_A5") (pintype "passive+no_connect"))
    )
    (net (code "70") (name "unconnected-(J2-CC2-PadB5)") (class "Default")
      (node (ref "J2") (pin "B5") (pinfunction "CC2_B5") (pintype "passive+no_connect"))
    )
    (net (code "71") (name "unconnected-(J2-RX1+-PadB11)") (class "Default")
      (node (ref "J2") (pin "B11") (pinfunction "RX1+_B11") (pintype "passive+no_connect"))
    )
    (net (code "72") (name "unconnected-(J2-RX1--PadB10)") (class "Default")
      (node (ref "J2") (pin "B10") (pinfunction "RX1-_B10") (pintype "passive+no_connect"))
    )
    (net (code "73") (name "unconnected-(J2-RX2+-PadA11)") (class "Default")
      (node (ref "J2") (pin "A11") (pinfunction "RX2+_A11") (pintype "passive+no_connect"))
    )
    (net (code "74") (name "unconnected-(J2-RX2--PadA10)") (class "Default")
      (node (ref "J2") (pin "A10") (pinfunction "RX2-_A10") (pintype "passive+no_connect"))
    )
    (net (code "75") (name "unconnected-(J2-SBU1-PadA8)") (class "Default")
      (node (ref "J2") (pin "A8") (pinfunction "SBU1_A8") (pintype "passive+no_connect"))
    )
    (net (code "76") (name "unconnected-(J2-SBU2-PadB8)") (class "Default")
      (node (ref "J2") (pin "B8") (pinfunction "SBU2_B8") (pintype "passive+no_connect"))
    )
    (net (code "77") (name "unconnected-(J2-TX1+-PadA2)") (class "Default")
      (node (ref "J2") (pin "A2") (pinfunction "TX1+_A2") (pintype "passive+no_connect"))
    )
    (net (code "78") (name "unconnected-(J2-TX1--PadA3)") (class "Default")
      (node (ref "J2") (pin "A3") (pinfunction "TX1-_A3") (pintype "passive+no_connect"))
    )
    (net (code "79") (name "unconnected-(J2-TX2+-PadB2)") (class "Default")
      (node (ref "J2") (pin "B2") (pinfunction "TX2+_B2") (pintype "passive+no_connect"))
    )
    (net (code "80") (name "unconnected-(J2-TX2--PadB3)") (class "Default")
      (node (ref "J2") (pin "B3") (pinfunction "TX2-_B3") (pintype "passive+no_connect"))
    )
    (net (code "81") (name "unconnected-(J3-Pad3)") (class "Default")
      (node (ref "J3") (pin "3") (pinfunction "3_3") (pintype "passive"))
    )
    (net (code "82") (name "unconnected-(J3-Pad4)") (class "Default")
      (node (ref "J3") (pin "4") (pinfunction "4_4") (pintype "passive"))
    )
    (net (code "83") (name "unconnected-(S1-2-Pad6)") (class "Default")
      (node (ref "S1") (pin "6") (pinfunction "2_6") (pintype "passive+no_connect"))
    )
    (net (code "84") (name "unconnected-(S2-2-Pad6)") (class "Default")
      (node (ref "S2") (pin "6") (pinfunction "2_6") (pintype "passive+no_connect"))
    )
    (net (code "85") (name "unconnected-(S3-2-Pad6)") (class "Default")
      (node (ref "S3") (pin "6") (pinfunction "2_6") (pintype "passive+no_connect"))
    )
    (net (code "86") (name "unconnected-(S4-2-Pad6)") (class "Default")
      (node (ref "S4") (pin "6") (pinfunction "2_6") (pintype "passive+no_connect"))
    )
    (net (code "87") (name "unconnected-(S5-2-Pad6)") (class "Default")
      (node (ref "S5") (pin "6") (pinfunction "2_6") (pintype "passive+no_connect"))
    )
    (net (code "88") (name "unconnected-(S6-2-Pad6)") (class "Default")
      (node (ref "S6") (pin "6") (pinfunction "2_6") (pintype "passive+no_connect"))
    )
    (net (code "89") (name "unconnected-(U1-AVCC-Pad24)") (class "Default")
      (node (ref "U1") (pin "24") (pinfunction "AVCC_24") (pintype "passive+no_connect"))
    )
    (net (code "90") (name "unconnected-(U1-CTS#-Pad11)") (class "Default")
      (node (ref "U1") (pin "11") (pinfunction "CTS#_11") (pintype "passive+no_connect"))
    )
    (net (code "91") (name "unconnected-(U1-DCD#-Pad10)") (class "Default")
      (node (ref "U1") (pin "10") (pinfunction "DCD#_10") (pintype "passive+no_connect"))
    )
    (net (code "92") (name "unconnected-(U1-DSR#-Pad9)") (class "Default")
      (node (ref "U1") (pin "9") (pinfunction "DSR#_9") (pintype "passive+no_connect"))
    )
    (net (code "93") (name "unconnected-(U1-DTR#-Pad2)") (class "Default")
      (node (ref "U1") (pin "2") (pinfunction "DTR#_2") (pintype "passive+no_connect"))
    )
    (net (code "94") (name "unconnected-(U1-GPIO2-Pad13)") (class "Default")
      (node (ref "U1") (pin "13") (pinfunction "GPIO2_13") (pintype "passive+no_connect"))
    )
    (net (code "95") (name "unconnected-(U1-GPIO3-Pad14)") (class "Default")
      (node (ref "U1") (pin "14") (pinfunction "GPIO3_14") (pintype "passive+no_connect"))
    )
    (net (code "96") (name "unconnected-(U1-OSCI-Pad27)") (class "Default")
      (node (ref "U1") (pin "27") (pinfunction "OSCI_27") (pintype "passive+no_connect"))
    )
    (net (code "97") (name "unconnected-(U1-OSCO-Pad28)") (class "Default")
      (node (ref "U1") (pin "28") (pinfunction "OSCO_28") (pintype "passive+no_connect"))
    )
    (net (code "98") (name "unconnected-(U1-RI#-Pad6)") (class "Default")
      (node (ref "U1") (pin "6") (pinfunction "RI#_6") (pintype "passive+no_connect"))
    )
    (net (code "99") (name "unconnected-(U1-RTS#-Pad3)") (class "Default")
      (node (ref "U1") (pin "3") (pinfunction "RTS#_3") (pintype "passive+no_connect"))
    )
    (net (code "100") (name "unconnected-(U1-SLEEP#-Pad12)") (class "Default")
      (node (ref "U1") (pin "12") (pinfunction "SLEEP#_12") (pintype "passive+no_connect"))
    )
    (net (code "101") (name "unconnected-(U1-VCC3I-Pad8)") (class "Default")
      (node (ref "U1") (pin "8") (pinfunction "VCC3I_8") (pintype "passive+no_connect"))
    )
    (net (code "102") (name "unconnected-(U2-OVCUR2-Pad19)") (class "Default")
      (node (ref "U2") (pin "19") (pinfunction "OVCUR2_19") (pintype "passive+no_connect"))
    )
    (net (code "103") (name "unconnected-(U2-PWREN1-Pad22)") (class "Default")
      (node (ref "U2") (pin "22") (pinfunction "PWREN1_22") (pintype "passive+no_connect"))
    )
    (net (code "104") (name "unconnected-(U2-PWREN2-Pad20)") (class "Default")
      (node (ref "U2") (pin "20") (pinfunction "PWREN2_20") (pintype "passive+no_connect"))
    )
    (net (code "105") (name "unconnected-(U2-TEST{slash}SCL-Pad14)") (class "Default")
      (node (ref "U2") (pin "14") (pinfunction "TEST/SCL_14") (pintype "passive+no_connect"))
    )
    (net (code "106") (name "unconnected-(U2-V5-Pad23)") (class "Default")
      (node (ref "U2") (pin "23") (pinfunction "V5_23") (pintype "passive+no_connect"))
    )
  )
)
